# ts9dx_redraw.net
KiCad netlist of a schematic drawn in EAGLE
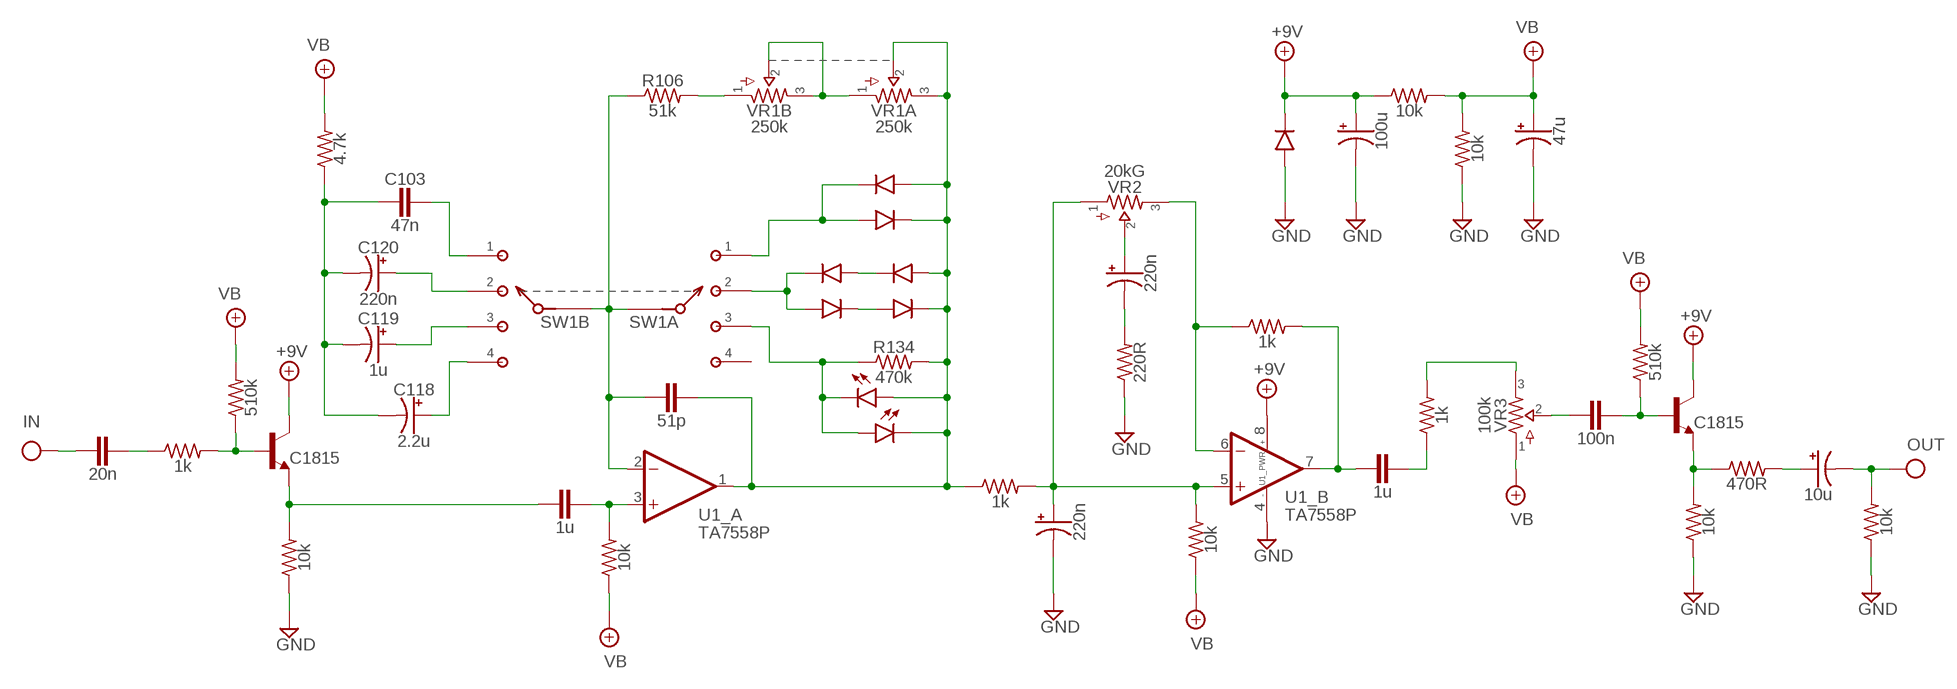
[diagram p0: schematic, sheet 1]

(export (version "E")
  (design (tool "Eeschema 10.0.6"))
  (components
    (comp (ref "C1")
      (value "51p")
      (footprint "eagle-import:BOX_SMALL")
      (libsource (lib "eagle-import") (part "CER/FILMBOX.1"))
    )
    (comp (ref "C101")
      (value "20n")
      (footprint "eagle-import:BOX_SMALL")
      (libsource (lib "eagle-import") (part "CER/FILMBOX.1"))
    )
    (comp (ref "C102")
      (value "1u")
      (footprint "eagle-import:BOX_SMALL")
      (libsource (lib "eagle-import") (part "CER/FILMBOX.1"))
    )
    (comp (ref "C103")
      (value "47n")
      (footprint "eagle-import:BOX_SMALL")
      (libsource (lib "eagle-import") (part "CER/FILMBOX.1"))
    )
    (comp (ref "C105")
      (value "220n")
      (footprint "eagle-import:050_020")
      (libsource (lib "eagle-import") (part "0500"))
    )
    (comp (ref "C106")
      (value "220n")
      (footprint "eagle-import:050_020")
      (libsource (lib "eagle-import") (part "0500"))
    )
    (comp (ref "C107")
      (value "1u")
      (footprint "eagle-import:BOX_SMALL")
      (libsource (lib "eagle-import") (part "CER/FILMBOX.1"))
    )
    (comp (ref "C108")
      (value "100n")
      (footprint "eagle-import:BOX_SMALL")
      (libsource (lib "eagle-import") (part "CER/FILMBOX.1"))
    )
    (comp (ref "C109")
      (value "10u")
      (footprint "eagle-import:050_020")
      (libsource (lib "eagle-import") (part "0500"))
    )
    (comp (ref "C116")
      (value "47u")
      (footprint "eagle-import:050_020")
      (libsource (lib "eagle-import") (part "0500"))
    )
    (comp (ref "C117")
      (value "100u")
      (footprint "eagle-import:050_020")
      (libsource (lib "eagle-import") (part "0500"))
    )
    (comp (ref "C118")
      (value "2.2u")
      (footprint "eagle-import:050_020")
      (libsource (lib "eagle-import") (part "0500"))
    )
    (comp (ref "C119")
      (value "1u")
      (footprint "eagle-import:050_020")
      (libsource (lib "eagle-import") (part "0500"))
    )
    (comp (ref "C120")
      (value "220n")
      (footprint "eagle-import:050_020")
      (libsource (lib "eagle-import") (part "0500"))
    )
    (comp (ref "D1")
      (value "DO35.2")
      (footprint "eagle-import:DO35-2")
      (libsource (lib "eagle-import") (part "DO35.2"))
    )
    (comp (ref "D2")
      (value "DO35.2")
      (footprint "eagle-import:DO35-2")
      (libsource (lib "eagle-import") (part "DO35.2"))
    )
    (comp (ref "D3")
      (value "DO35.2")
      (footprint "eagle-import:DO35-2")
      (libsource (lib "eagle-import") (part "DO35.2"))
    )
    (comp (ref "D4")
      (value "DO35.2")
      (footprint "eagle-import:DO35-2")
      (libsource (lib "eagle-import") (part "DO35.2"))
    )
    (comp (ref "D5")
      (value "LED")
      (footprint "eagle-import:3MM_D")
      (libsource (lib "eagle-import") (part "LED"))
    )
    (comp (ref "D6")
      (value "LED")
      (footprint "eagle-import:3MM_D")
      (libsource (lib "eagle-import") (part "LED"))
    )
    (comp (ref "D7")
      (value "DO35.2")
      (footprint "eagle-import:DO35-2")
      (libsource (lib "eagle-import") (part "DO35.2"))
    )
    (comp (ref "D8")
      (value "DO35.2")
      (footprint "eagle-import:DO35-2")
      (libsource (lib "eagle-import") (part "DO35.2"))
    )
    (comp (ref "D108")
      (value "DO35.2")
      (footprint "eagle-import:DO35-2")
      (libsource (lib "eagle-import") (part "DO35.2"))
    )
    (comp (ref "Q101")
      (value "C1815")
      (footprint "eagle-import:TO92-")
      (libsource (lib "eagle-import") (part "2N3904"))
    )
    (comp (ref "Q103")
      (value "C1815")
      (footprint "eagle-import:TO92-")
      (libsource (lib "eagle-import") (part "2N3904"))
    )
    (comp (ref "R3")
      (value "4.7k")
      (footprint "eagle-import:R0207_3")
      (libsource (lib "eagle-import") (part "R_.3B"))
    )
    (comp (ref "R101")
      (value "1k")
      (footprint "eagle-import:R0207_3")
      (libsource (lib "eagle-import") (part "R_.3B"))
    )
    (comp (ref "R102")
      (value "510k")
      (footprint "eagle-import:R0207_3")
      (libsource (lib "eagle-import") (part "R_.3B"))
    )
    (comp (ref "R103")
      (value "10k")
      (footprint "eagle-import:R0207_3")
      (libsource (lib "eagle-import") (part "R_.3B"))
    )
    (comp (ref "R105")
      (value "10k")
      (footprint "eagle-import:R0207_3")
      (libsource (lib "eagle-import") (part "R_.3B"))
    )
    (comp (ref "R106")
      (value "51k")
      (footprint "eagle-import:R0207_3")
      (libsource (lib "eagle-import") (part "R_.3B"))
    )
    (comp (ref "R107")
      (value "1k")
      (footprint "eagle-import:R0207_3")
      (libsource (lib "eagle-import") (part "R_.3B"))
    )
    (comp (ref "R108")
      (value "220R")
      (footprint "eagle-import:R0207_3")
      (libsource (lib "eagle-import") (part "R_.3B"))
    )
    (comp (ref "R109")
      (value "10k")
      (footprint "eagle-import:R0207_3")
      (libsource (lib "eagle-import") (part "R_.3B"))
    )
    (comp (ref "R110")
      (value "1k")
      (footprint "eagle-import:R0207_3")
      (libsource (lib "eagle-import") (part "R_.3B"))
    )
    (comp (ref "R111")
      (value "1k")
      (footprint "eagle-import:R0207_3")
      (libsource (lib "eagle-import") (part "R_.3B"))
    )
    (comp (ref "R112")
      (value "510k")
      (footprint "eagle-import:R0207_3")
      (libsource (lib "eagle-import") (part "R_.3B"))
    )
    (comp (ref "R113")
      (value "10k")
      (footprint "eagle-import:R0207_3")
      (libsource (lib "eagle-import") (part "R_.3B"))
    )
    (comp (ref "R114")
      (value "470R")
      (footprint "eagle-import:R0207_3")
      (libsource (lib "eagle-import") (part "R_.3B"))
    )
    (comp (ref "R115")
      (value "10k")
      (footprint "eagle-import:R0207_3")
      (libsource (lib "eagle-import") (part "R_.3B"))
    )
    (comp (ref "R132")
      (value "10k")
      (footprint "eagle-import:R0207_3")
      (libsource (lib "eagle-import") (part "R_.3B"))
    )
    (comp (ref "R133")
      (value "10k")
      (footprint "eagle-import:R0207_3")
      (libsource (lib "eagle-import") (part "R_.3B"))
    )
    (comp (ref "R134")
      (value "470k")
      (footprint "eagle-import:R0207_3")
      (libsource (lib "eagle-import") (part "R_.3B"))
    )
    (comp (ref "SW1")
      (value "2P4T")
      (footprint "eagle-import:SMALLROTARY")
      (libsource (lib "eagle-import") (part "2P4T"))
    )
    (comp (ref "U1")
      (value "TA7558P")
      (footprint "eagle-import:DIL0")
      (libsource (lib "eagle-import") (part "DUALTH"))
    )
    (comp (ref "VR1A")
      (value "250k")
      (footprint "eagle-import:16MM")
      (libsource (lib "eagle-import") (part "POTS16MM"))
    )
    (comp (ref "VR1B")
      (value "250k")
      (footprint "eagle-import:16MM")
      (libsource (lib "eagle-import") (part "POTS16MM"))
    )
    (comp (ref "VR2")
      (value "20kG")
      (footprint "eagle-import:16MM")
      (libsource (lib "eagle-import") (part "POTS16MM"))
    )
    (comp (ref "VR3")
      (value "100k")
      (footprint "eagle-import:16MM")
      (libsource (lib "eagle-import") (part "POTS16MM"))
    )
  )
  (nets
    (net (code "1") (name "+9V") (class "Default")
      (node (ref "C117") (pin "+") (pinfunction "+_+") (pintype "passive"))
      (node (ref "D108") (pin "C") (pinfunction "C_C") (pintype "passive"))
      (node (ref "Q101") (pin "1") (pinfunction "C_1") (pintype "passive"))
      (node (ref "Q103") (pin "1") (pinfunction "C_1") (pintype "passive"))
      (node (ref "R133") (pin "1") (pinfunction "1_1") (pintype "passive"))
      (node (ref "U1") (pin "8") (pinfunction "V+_8") (pintype "power_in"))
    )
    (net (code "2") (name "GND") (class "Default")
      (node (ref "C105") (pin "-") (pinfunction "-_-") (pintype "passive"))
      (node (ref "C116") (pin "-") (pinfunction "-_-") (pintype "passive"))
      (node (ref "C117") (pin "-") (pinfunction "-_-") (pintype "passive"))
      (node (ref "D108") (pin "A") (pinfunction "A_A") (pintype "passive"))
      (node (ref "R103") (pin "1") (pinfunction "1_1") (pintype "passive"))
      (node (ref "R108") (pin "1") (pinfunction "1_1") (pintype "passive"))
      (node (ref "R113") (pin "1") (pinfunction "1_1") (pintype "passive"))
      (node (ref "R115") (pin "1") (pinfunction "1_1") (pintype "passive"))
      (node (ref "R132") (pin "1") (pinfunction "1_1") (pintype "passive"))
      (node (ref "U1") (pin "4") (pinfunction "V-_4") (pintype "power_in"))
    )
    (net (code "3") (name "IN") (class "Default")
      (node (ref "C101") (pin "2") (pinfunction "2_2") (pintype "passive"))
    )
    (net (code "4") (name "Net-(C101-Pad1)") (class "Default")
      (node (ref "C101") (pin "1") (pinfunction "1_1") (pintype "passive"))
      (node (ref "R101") (pin "1") (pinfunction "1_1") (pintype "passive"))
    )
    (net (code "5") (name "Net-(C103-Pad2)") (class "Default")
      (node (ref "C103") (pin "2") (pinfunction "2_2") (pintype "passive"))
      (node (ref "C118") (pin "-") (pinfunction "-_-") (pintype "passive"))
      (node (ref "C119") (pin "-") (pinfunction "-_-") (pintype "passive"))
      (node (ref "C120") (pin "-") (pinfunction "-_-") (pintype "passive"))
      (node (ref "R3") (pin "1") (pinfunction "1_1") (pintype "passive"))
    )
    (net (code "6") (name "Net-(C106-Pad+)") (class "Default")
      (node (ref "C106") (pin "+") (pinfunction "+_+") (pintype "passive"))
      (node (ref "VR2") (pin "2") (pinfunction "2_2") (pintype "passive"))
    )
    (net (code "7") (name "Net-(C106-Pad-)") (class "Default")
      (node (ref "C106") (pin "-") (pinfunction "-_-") (pintype "passive"))
      (node (ref "R108") (pin "2") (pinfunction "2_2") (pintype "passive"))
    )
    (net (code "8") (name "Net-(C107-Pad1)") (class "Default")
      (node (ref "C107") (pin "1") (pinfunction "1_1") (pintype "passive"))
      (node (ref "R111") (pin "1") (pinfunction "1_1") (pintype "passive"))
    )
    (net (code "9") (name "Net-(C108-Pad2)") (class "Default")
      (node (ref "C108") (pin "2") (pinfunction "2_2") (pintype "passive"))
      (node (ref "VR3") (pin "2") (pinfunction "2_2") (pintype "passive"))
    )
    (net (code "10") (name "Net-(C109-Pad+)") (class "Default")
      (node (ref "C109") (pin "+") (pinfunction "+_+") (pintype "passive"))
      (node (ref "R114") (pin "2") (pinfunction "2_2") (pintype "passive"))
    )
    (net (code "11") (name "Net-(D1-PadA)") (class "Default")
      (node (ref "D1") (pin "A") (pinfunction "A_A") (pintype "passive"))
      (node (ref "D4") (pin "C") (pinfunction "C_C") (pintype "passive"))
      (node (ref "SW1") (pin "2") (pinfunction "2_2") (pintype "bidirectional"))
    )
    (net (code "12") (name "Net-(D1-PadC)") (class "Default")
      (node (ref "D1") (pin "C") (pinfunction "C_C") (pintype "passive"))
      (node (ref "D2") (pin "A") (pinfunction "A_A") (pintype "passive"))
    )
    (net (code "13") (name "Net-(D3-PadC)") (class "Default")
      (node (ref "D3") (pin "C") (pinfunction "C_C") (pintype "passive"))
      (node (ref "D4") (pin "A") (pinfunction "A_A") (pintype "passive"))
    )
    (net (code "14") (name "Net-(D5-A)") (class "Default")
      (node (ref "C1") (pin "1") (pinfunction "1_1") (pintype "passive"))
      (node (ref "D2") (pin "C") (pinfunction "C_C") (pintype "passive"))
      (node (ref "D3") (pin "A") (pinfunction "A_A") (pintype "passive"))
      (node (ref "D5") (pin "ANODE") (pinfunction "A_ANODE") (pintype "passive"))
      (node (ref "D6") (pin "P$1") (pinfunction "C_P$1") (pintype "passive"))
      (node (ref "D7") (pin "C") (pinfunction "C_C") (pintype "passive"))
      (node (ref "D8") (pin "A") (pinfunction "A_A") (pintype "passive"))
      (node (ref "R107") (pin "1") (pinfunction "1_1") (pintype "passive"))
      (node (ref "R134") (pin "2") (pinfunction "2_2") (pintype "passive"))
      (node (ref "U1") (pin "1") (pinfunction "OUT_1") (pintype "output"))
      (node (ref "VR1A") (pin "2") (pinfunction "2_2") (pintype "passive"))
      (node (ref "VR1A") (pin "3") (pinfunction "3_3") (pintype "passive"))
    )
    (net (code "15") (name "Net-(D5-C)") (class "Default")
      (node (ref "D5") (pin "P$1") (pinfunction "C_P$1") (pintype "passive"))
      (node (ref "D6") (pin "ANODE") (pinfunction "A_ANODE") (pintype "passive"))
      (node (ref "R134") (pin "1") (pinfunction "1_1") (pintype "passive"))
      (node (ref "SW1") (pin "3") (pinfunction "3_3") (pintype "bidirectional"))
    )
    (net (code "16") (name "Net-(D7-PadA)") (class "Default")
      (node (ref "D7") (pin "A") (pinfunction "A_A") (pintype "passive"))
      (node (ref "D8") (pin "C") (pinfunction "C_C") (pintype "passive"))
      (node (ref "SW1") (pin "1") (pinfunction "1_1") (pintype "bidirectional"))
    )
    (net (code "17") (name "Net-(Q101-B)") (class "Default")
      (node (ref "Q101") (pin "2") (pinfunction "B_2") (pintype "passive"))
      (node (ref "R101") (pin "2") (pinfunction "2_2") (pintype "passive"))
      (node (ref "R102") (pin "1") (pinfunction "1_1") (pintype "passive"))
    )
    (net (code "18") (name "Net-(Q101-E)") (class "Default")
      (node (ref "C102") (pin "2") (pinfunction "2_2") (pintype "passive"))
      (node (ref "Q101") (pin "3") (pinfunction "E_3") (pintype "passive"))
      (node (ref "R103") (pin "2") (pinfunction "2_2") (pintype "passive"))
    )
    (net (code "19") (name "Net-(Q103-B)") (class "Default")
      (node (ref "C108") (pin "1") (pinfunction "1_1") (pintype "passive"))
      (node (ref "Q103") (pin "2") (pinfunction "B_2") (pintype "passive"))
      (node (ref "R112") (pin "1") (pinfunction "1_1") (pintype "passive"))
    )
    (net (code "20") (name "Net-(Q103-E)") (class "Default")
      (node (ref "Q103") (pin "3") (pinfunction "E_3") (pintype "passive"))
      (node (ref "R113") (pin "2") (pinfunction "2_2") (pintype "passive"))
      (node (ref "R114") (pin "1") (pinfunction "1_1") (pintype "passive"))
    )
    (net (code "21") (name "Net-(R106-Pad2)") (class "Default")
      (node (ref "R106") (pin "2") (pinfunction "2_2") (pintype "passive"))
      (node (ref "VR1B") (pin "1") (pinfunction "1_1") (pintype "passive"))
    )
    (net (code "22") (name "Net-(R111-Pad2)") (class "Default")
      (node (ref "R111") (pin "2") (pinfunction "2_2") (pintype "passive"))
      (node (ref "VR3") (pin "3") (pinfunction "3_3") (pintype "passive"))
    )
    (net (code "23") (name "Net-(SW1A-A)") (class "Default")
      (node (ref "C1") (pin "2") (pinfunction "2_2") (pintype "passive"))
      (node (ref "R106") (pin "1") (pinfunction "1_1") (pintype "passive"))
      (node (ref "SW1") (pin "9") (pinfunction "A_9") (pintype "bidirectional"))
      (node (ref "SW1") (pin "C") (pinfunction "A_C") (pintype "bidirectional"))
      (node (ref "U1") (pin "2") (pinfunction "-IN_2") (pintype "input"))
    )
    (net (code "24") (name "Net-(SW1B-1)") (class "Default")
      (node (ref "C103") (pin "1") (pinfunction "1_1") (pintype "passive"))
      (node (ref "SW1") (pin "5") (pinfunction "1_5") (pintype "bidirectional"))
    )
    (net (code "25") (name "Net-(SW1B-2)") (class "Default")
      (node (ref "C120") (pin "+") (pinfunction "+_+") (pintype "passive"))
      (node (ref "SW1") (pin "6") (pinfunction "2_6") (pintype "bidirectional"))
    )
    (net (code "26") (name "Net-(SW1B-3)") (class "Default")
      (node (ref "C119") (pin "+") (pinfunction "+_+") (pintype "passive"))
      (node (ref "SW1") (pin "7") (pinfunction "3_7") (pintype "bidirectional"))
    )
    (net (code "27") (name "Net-(SW1B-4)") (class "Default")
      (node (ref "C118") (pin "+") (pinfunction "+_+") (pintype "passive"))
      (node (ref "SW1") (pin "8") (pinfunction "4_8") (pintype "bidirectional"))
    )
    (net (code "28") (name "Net-(U1A-+IN)") (class "Default")
      (node (ref "C102") (pin "1") (pinfunction "1_1") (pintype "passive"))
      (node (ref "R105") (pin "2") (pinfunction "2_2") (pintype "passive"))
      (node (ref "U1") (pin "3") (pinfunction "+IN_3") (pintype "input"))
    )
    (net (code "29") (name "Net-(U1B-+IN)") (class "Default")
      (node (ref "C105") (pin "+") (pinfunction "+_+") (pintype "passive"))
      (node (ref "R107") (pin "2") (pinfunction "2_2") (pintype "passive"))
      (node (ref "R109") (pin "2") (pinfunction "2_2") (pintype "passive"))
      (node (ref "U1") (pin "5") (pinfunction "+IN_5") (pintype "input"))
      (node (ref "VR2") (pin "1") (pinfunction "1_1") (pintype "passive"))
    )
    (net (code "30") (name "Net-(U1B--IN)") (class "Default")
      (node (ref "R110") (pin "1") (pinfunction "1_1") (pintype "passive"))
      (node (ref "U1") (pin "6") (pinfunction "-IN_6") (pintype "input"))
      (node (ref "VR2") (pin "3") (pinfunction "3_3") (pintype "passive"))
    )
    (net (code "31") (name "Net-(U1B-OUT)") (class "Default")
      (node (ref "C107") (pin "2") (pinfunction "2_2") (pintype "passive"))
      (node (ref "R110") (pin "2") (pinfunction "2_2") (pintype "passive"))
      (node (ref "U1") (pin "7") (pinfunction "OUT_7") (pintype "output"))
    )
    (net (code "32") (name "Net-(VR1A-Pad1)") (class "Default")
      (node (ref "VR1A") (pin "1") (pinfunction "1_1") (pintype "passive"))
      (node (ref "VR1B") (pin "2") (pinfunction "2_2") (pintype "passive"))
      (node (ref "VR1B") (pin "3") (pinfunction "3_3") (pintype "passive"))
    )
    (net (code "33") (name "OUT") (class "Default")
      (node (ref "C109") (pin "-") (pinfunction "-_-") (pintype "passive"))
      (node (ref "R115") (pin "2") (pinfunction "2_2") (pintype "passive"))
    )
    (net (code "34") (name "VB") (class "Default")
      (node (ref "C116") (pin "+") (pinfunction "+_+") (pintype "passive"))
      (node (ref "R102") (pin "2") (pinfunction "2_2") (pintype "passive"))
      (node (ref "R105") (pin "1") (pinfunction "1_1") (pintype "passive"))
      (node (ref "R109") (pin "1") (pinfunction "1_1") (pintype "passive"))
      (node (ref "R112") (pin "2") (pinfunction "2_2") (pintype "passive"))
      (node (ref "R132") (pin "2") (pinfunction "2_2") (pintype "passive"))
      (node (ref "R133") (pin "2") (pinfunction "2_2") (pintype "passive"))
      (node (ref "R3") (pin "2") (pinfunction "2_2") (pintype "passive"))
      (node (ref "VR3") (pin "1") (pinfunction "1_1") (pintype "passive"))
    )
    (net (code "35") (name "unconnected-(SW1-Pad4)") (class "Default")
      (node (ref "SW1") (pin "4") (pinfunction "4_4") (pintype "bidirectional"))
    )
  )
)
